# TopSheet.net
KiCad netlist of a schematic drawn in Altium Designer
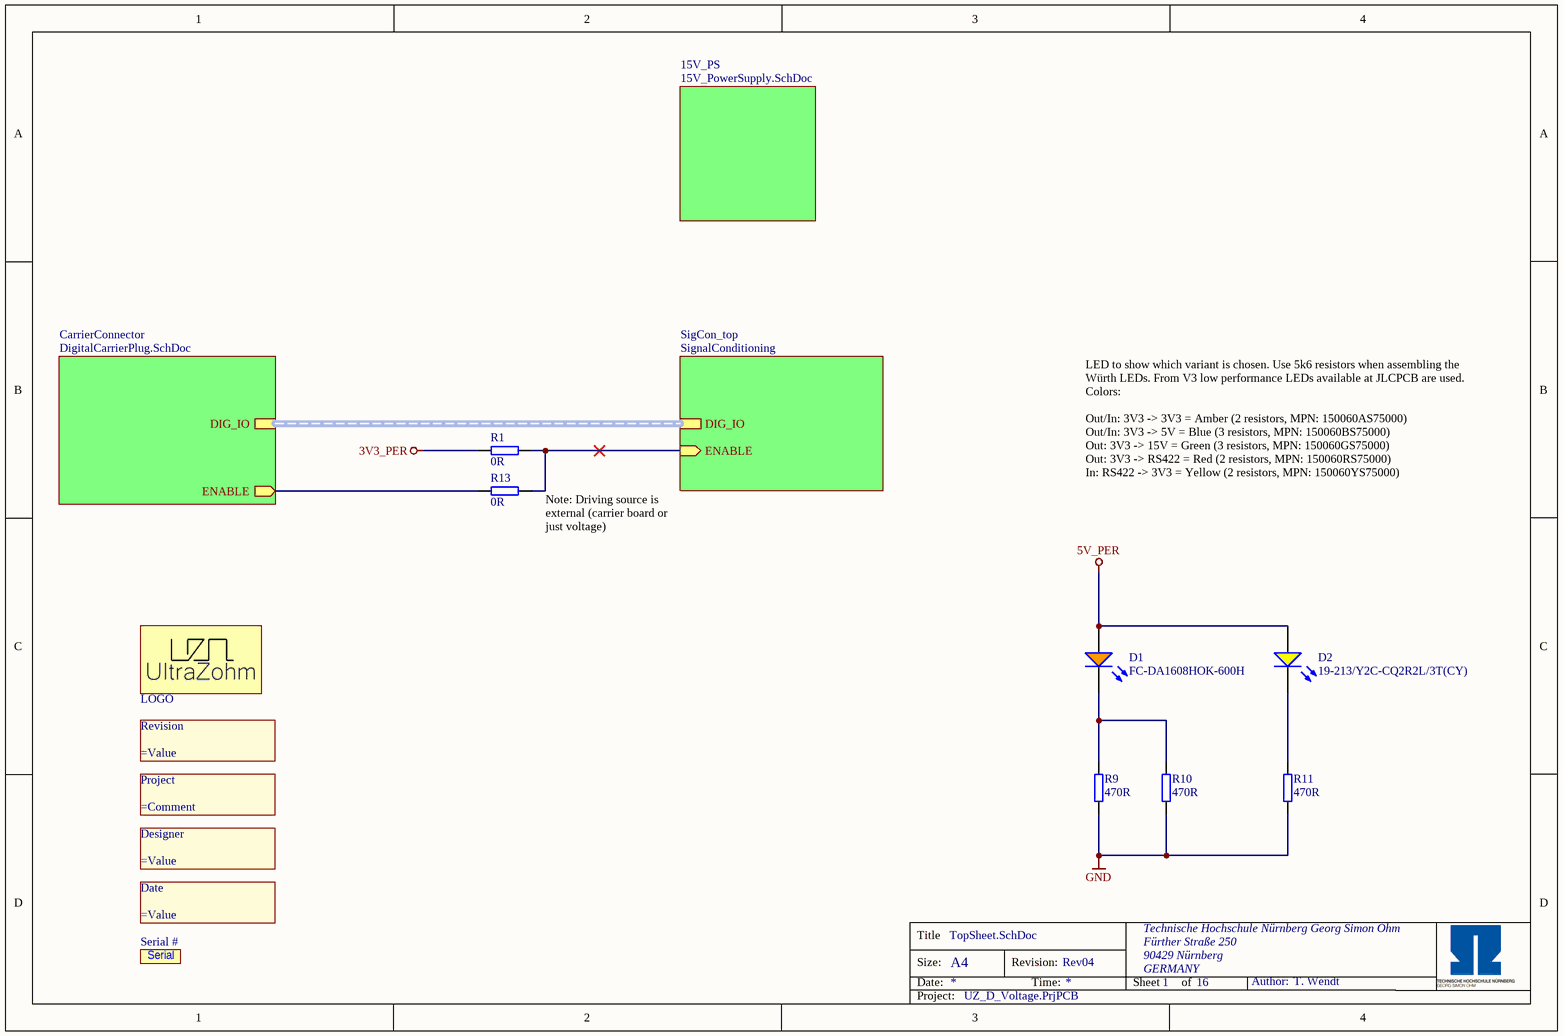
[diagram p0: TopSheet.SchDoc]

(export (version "E")
  (design (tool "Eeschema 10.0.6"))
  (components
    (comp (ref "D1")
      (value "FC-DA1608HOK-600H")
      (footprint "WL-SMCW_0603")
      (description "LED ORANGE 600~610NM 80~220MCD@20MA TOP VIEW 0603 ROHS")
      (fields
        (field (name "MANUFACTURER") "Foshan NationStar Optoelectronics")
        (field (name "LCSC PART NUMBER") "C84269")
        (field (name "CREATED FROM") "T. Wendt")
      )
      (libsource (lib "user") (part "LED_Amber"))
    )
    (comp (ref "D2")
      (value "19-213/Y2C-CQ2R2L/3T(CY)")
      (footprint "WL-SMCW_0603")
      (description "LED YELLOW 585.5~591.5NM 90~180MCD@20MA TOP VIEW 0603 ROHS")
      (fields
        (field (name "MANUFACTURER") "Everlight Elec")
        (field (name "LCSC PART NUMBER") "C72038")
        (field (name "CREATED FROM") "T. Wendt")
      )
      (libsource (lib "user") (part "LED_Yellow"))
    )
    (comp (ref "Date")
      (value "~")
      (footprint "COMMENT")
      (fields
        (field (name "MANUFACTURER") "PCB Manufacturer")
        (field (name "MANUFACTURER PART NUMBER") "Project End Date")
        (field (name "CREATED FROM") "T. Wendt")
      )
      (libsource (lib "user") (part "Date"))
    )
    (comp (ref "Designer")
      (value "~")
      (footprint "Designator:comment")
      (fields
        (field (name "MANUFACTURER") "PCB Manufacturer")
        (field (name "MANUFACTURER PART NUMBER") "Project Author")
        (field (name "CREATED FROM") "T. Wendt")
      )
      (libsource (lib "user") (part "ProjectAuthor"))
    )
    (comp (ref "LOGO")
      (value "UZ Logo")
      (footprint "UZ_Logo_small")
      (description "Official Project Logo of the UltraZohm")
      (fields (field (name "CREATED FROM") "T. Wendt"))
      (libsource (lib "user") (part "UZ_LOGO"))
    )
    (comp (ref "Project")
      (value "~")
      (footprint "COMMENT")
      (fields
        (field (name "MANUFACTURER") "PCB Manufacturer")
        (field (name "MANUFACTURER PART NUMBER") "Project Name")
        (field (name "CREATED FROM") "T. Wendt")
      )
      (libsource (lib "user") (part "ProjectName"))
    )
    (comp (ref "R1")
      (value "0R")
      (footprint "RES 0603_1608")
      (description "SMD resistor E24 series")
      (fields
        (field (name "MANUFACTURER PART NUMBER") "RC0603JR-070RL")
        (field (name "MANUFACTURER") "YAGEO")
        (field (name "CREATED FROM") "MGremer")
      )
      (libsource (lib "user") (part "Resistor"))
    )
    (comp (ref "R9")
      (value "470R")
      (footprint "RES 0603_1608")
      (description "SMD resistor E24 series")
      (fields
        (field (name "MANUFACTURER PART NUMBER") "RK73B1JTTD471J")
        (field (name "MANUFACTURER") "KOA Speer")
        (field (name "CREATED FROM") "MGremer")
      )
      (libsource (lib "user") (part "Resistor"))
    )
    (comp (ref "R10")
      (value "470R")
      (footprint "RES 0603_1608")
      (description "SMD resistor E24 series")
      (fields
        (field (name "MANUFACTURER PART NUMBER") "RK73B1JTTD471J")
        (field (name "MANUFACTURER") "KOA Speer")
        (field (name "CREATED FROM") "MGremer")
      )
      (libsource (lib "user") (part "Resistor"))
    )
    (comp (ref "R11")
      (value "470R")
      (footprint "RES 0603_1608")
      (description "SMD resistor E24 series")
      (fields
        (field (name "MANUFACTURER PART NUMBER") "RK73B1JTTD471J")
        (field (name "MANUFACTURER") "KOA Speer")
        (field (name "CREATED FROM") "MGremer")
      )
      (libsource (lib "user") (part "Resistor"))
    )
    (comp (ref "R13")
      (value "0R")
      (footprint "RES 0603_1608")
      (description "SMD resistor E24 series")
      (fields
        (field (name "MANUFACTURER PART NUMBER") "RC0603JR-070RL")
        (field (name "MANUFACTURER") "YAGEO")
        (field (name "CREATED FROM") "MGremer")
      )
      (libsource (lib "user") (part "Resistor"))
    )
    (comp (ref "Revision")
      (value "~")
      (footprint "Designator:comment")
      (fields
        (field (name "MANUFACTURER") "PCB Manufacturer")
        (field (name "MANUFACTURER PART NUMBER") "Project Revision")
        (field (name "CREATED FROM") "T. Wendt")
      )
      (libsource (lib "user") (part "ProjectRevision"))
    )
    (comp (ref "Serial")
      (value "Serial #")
      (footprint "SERIAL")
      (description "Field to put in a serial number")
      (fields
        (field (name "MANUFACTURER") "PCB Manufacturer")
        (field (name "MANUFACTURER PART NUMBER") "Serial Number")
        (field (name "CREATED FROM") "T. Wendt")
      )
      (libsource (lib "user") (part "SerialNumber"))
    )
  )
  (nets
    (net (code "2") (name "/ENABLE") (class "Default")
      (node (ref "R1") (pin "2") (pinfunction "2_2") (pintype "passive"))
      (node (ref "R13") (pin "2") (pinfunction "2_2") (pintype "passive"))
    )
    (net (code "3") (name "/ENABLE_1") (class "Default")
      (node (ref "R13") (pin "1") (pinfunction "1_1") (pintype "passive"))
    )
    (net (code "4") (name "3V3_PER") (class "Default")
      (node (ref "R1") (pin "1") (pinfunction "1_1") (pintype "passive"))
    )
    (net (code "5") (name "5V_PER") (class "Default")
      (node (ref "D1") (pin "2") (pinfunction "A_2") (pintype "passive"))
      (node (ref "D2") (pin "2") (pinfunction "A_2") (pintype "passive"))
    )
    (net (code "6") (name "GND") (class "Default")
      (node (ref "R10") (pin "1") (pinfunction "1_1") (pintype "passive"))
      (node (ref "R11") (pin "1") (pinfunction "1_1") (pintype "passive"))
      (node (ref "R9") (pin "1") (pinfunction "1_1") (pintype "passive"))
    )
    (net (code "7") (name "Net-(D1-K)") (class "Default")
      (node (ref "D1") (pin "1") (pinfunction "K_1") (pintype "passive"))
      (node (ref "R10") (pin "2") (pinfunction "2_2") (pintype "passive"))
      (node (ref "R9") (pin "2") (pinfunction "2_2") (pintype "passive"))
    )
    (net (code "8") (name "Net-(D2-K)") (class "Default")
      (node (ref "D2") (pin "1") (pinfunction "K_1") (pintype "passive"))
      (node (ref "R11") (pin "2") (pinfunction "2_2") (pintype "passive"))
    )
  )
)
